# eightbyeight-testcard.net
KiCad netlist of a schematic drawn in EAGLE
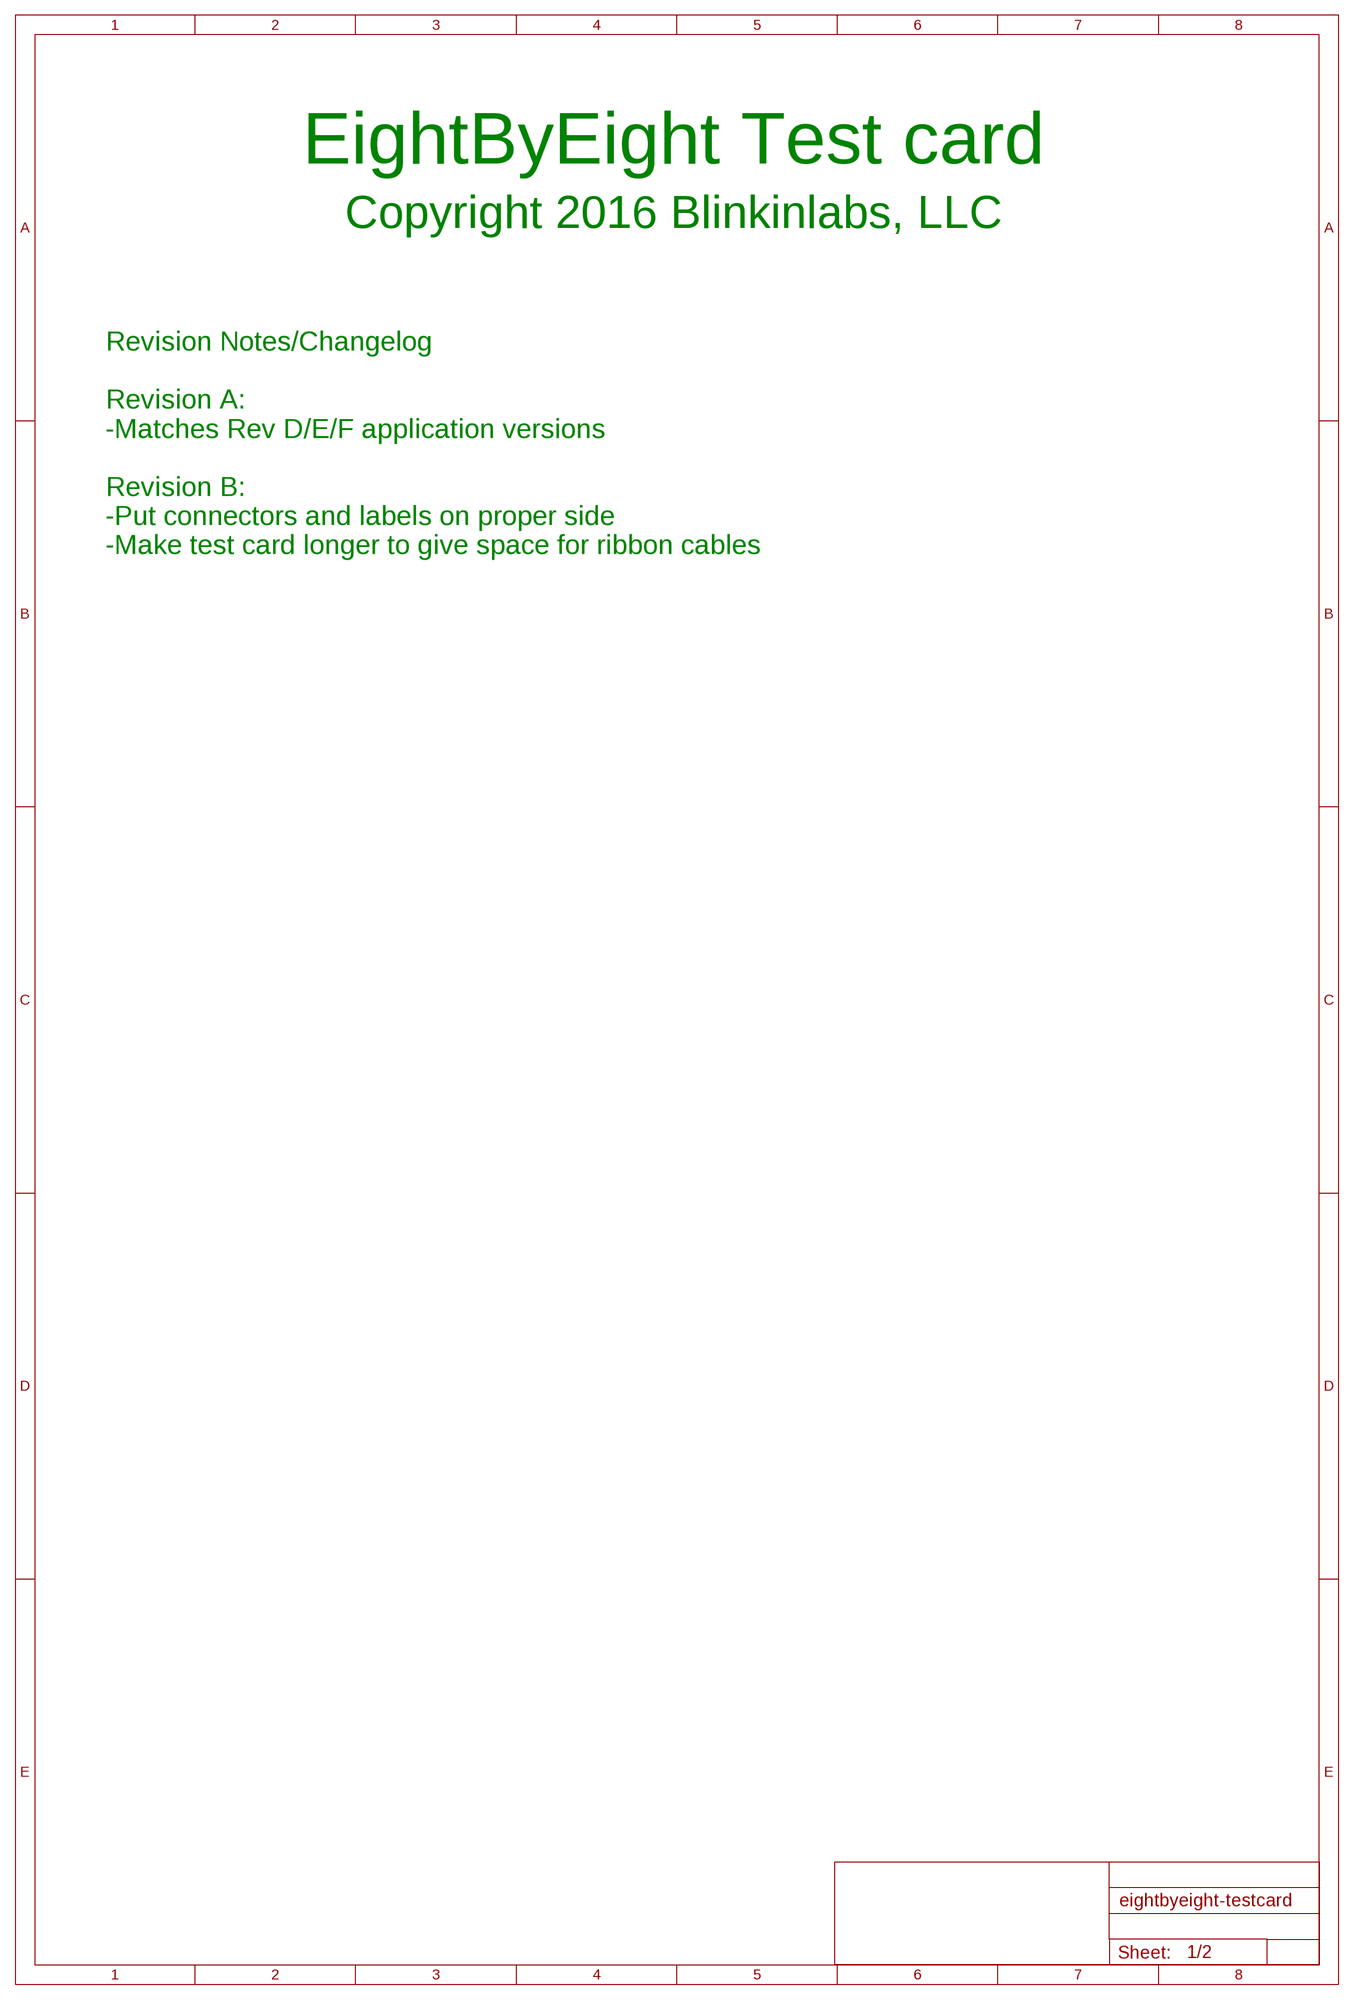
[diagram p0: schematic, sheet 1]
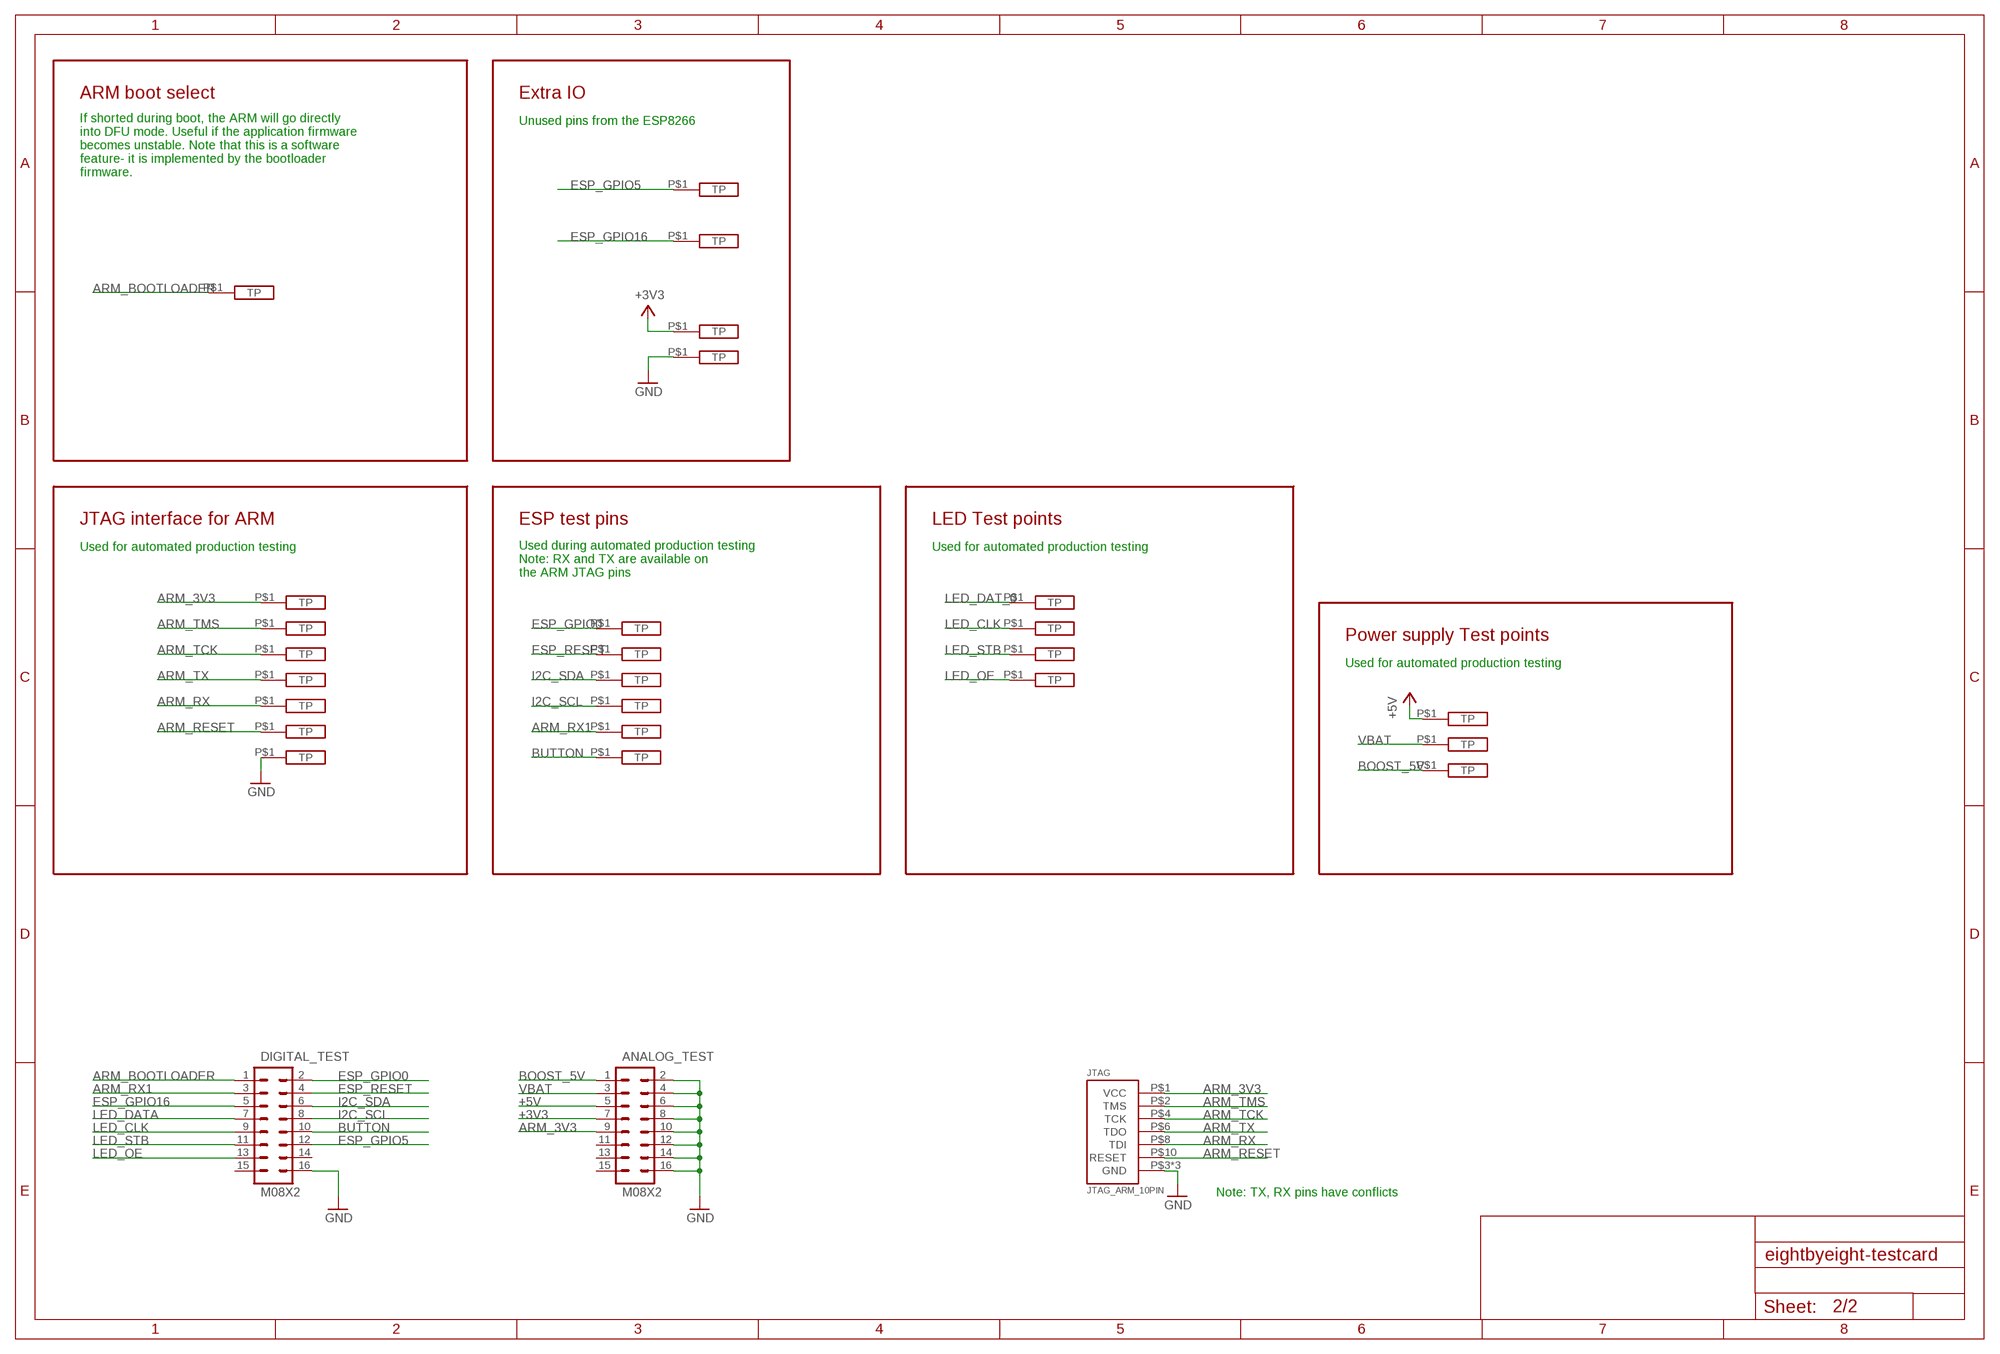
[diagram p1: schematic, sheet 2]

(export (version "E")
  (design (tool "Eeschema 10.0.6"))
  (components
    (comp (ref "+3V3")
      (value "TEST_POINT2.55MM")
      (footprint "eagle-import:IO_HOLE_2.55MM")
      (libsource (lib "eagle-import") (part "TEST_POINT2.55MM"))
    )
    (comp (ref "5V")
      (value "TEST_POINT1.4MM")
      (footprint "eagle-import:IO_HOLE_1.4MM")
      (libsource (lib "eagle-import") (part "TEST_POINT1.4MM"))
    )
    (comp (ref "ANALOG_TEST")
      (value "M08X2")
      (footprint "eagle-import:2X8")
      (libsource (lib "eagle-import") (part "M08X2"))
    )
    (comp (ref "ARM_3V3")
      (value "TEST_POINT1.4MM")
      (footprint "eagle-import:IO_HOLE_1.4MM")
      (libsource (lib "eagle-import") (part "TEST_POINT1.4MM"))
    )
    (comp (ref "ARM_BOOT")
      (value "TEST_POINT1.4MM")
      (footprint "eagle-import:IO_HOLE_1.4MM")
      (libsource (lib "eagle-import") (part "TEST_POINT1.4MM"))
    )
    (comp (ref "ARM_RESET")
      (value "TEST_POINT1.4MM")
      (footprint "eagle-import:IO_HOLE_1.4MM")
      (libsource (lib "eagle-import") (part "TEST_POINT1.4MM"))
    )
    (comp (ref "ARM_RX")
      (value "TEST_POINT1.4MM")
      (footprint "eagle-import:IO_HOLE_1.4MM")
      (libsource (lib "eagle-import") (part "TEST_POINT1.4MM"))
    )
    (comp (ref "ARM_RX1")
      (value "TEST_POINT1.4MM")
      (footprint "eagle-import:IO_HOLE_1.4MM")
      (libsource (lib "eagle-import") (part "TEST_POINT1.4MM"))
    )
    (comp (ref "ARM_TCK")
      (value "TEST_POINT1.4MM")
      (footprint "eagle-import:IO_HOLE_1.4MM")
      (libsource (lib "eagle-import") (part "TEST_POINT1.4MM"))
    )
    (comp (ref "ARM_TMS")
      (value "TEST_POINT1.4MM")
      (footprint "eagle-import:IO_HOLE_1.4MM")
      (libsource (lib "eagle-import") (part "TEST_POINT1.4MM"))
    )
    (comp (ref "ARM_TX")
      (value "TEST_POINT1.4MM")
      (footprint "eagle-import:IO_HOLE_1.4MM")
      (libsource (lib "eagle-import") (part "TEST_POINT1.4MM"))
    )
    (comp (ref "BOOST_5V")
      (value "TEST_POINT1.4MM")
      (footprint "eagle-import:IO_HOLE_1.4MM")
      (libsource (lib "eagle-import") (part "TEST_POINT1.4MM"))
    )
    (comp (ref "BUTTON")
      (value "TEST_POINT1.4MM")
      (footprint "eagle-import:IO_HOLE_1.4MM")
      (libsource (lib "eagle-import") (part "TEST_POINT1.4MM"))
    )
    (comp (ref "DIGITAL_TEST")
      (value "M08X2")
      (footprint "eagle-import:2X8")
      (libsource (lib "eagle-import") (part "M08X2"))
    )
    (comp (ref "ESP_GPIO0")
      (value "TEST_POINT1.4MM")
      (footprint "eagle-import:IO_HOLE_1.4MM")
      (libsource (lib "eagle-import") (part "TEST_POINT1.4MM"))
    )
    (comp (ref "ESP_GPIO5")
      (value "TEST_POINT2.55MM")
      (footprint "eagle-import:IO_HOLE_2.55MM")
      (libsource (lib "eagle-import") (part "TEST_POINT2.55MM"))
    )
    (comp (ref "ESP_GPIO16")
      (value "TEST_POINT2.55MM")
      (footprint "eagle-import:IO_HOLE_2.55MM")
      (libsource (lib "eagle-import") (part "TEST_POINT2.55MM"))
    )
    (comp (ref "ESP_RESET")
      (value "TEST_POINT1.4MM")
      (footprint "eagle-import:IO_HOLE_1.4MM")
      (libsource (lib "eagle-import") (part "TEST_POINT1.4MM"))
    )
    (comp (ref "GND")
      (value "TEST_POINT2.55MM")
      (footprint "eagle-import:IO_HOLE_2.55MM")
      (libsource (lib "eagle-import") (part "TEST_POINT2.55MM"))
    )
    (comp (ref "GND_")
      (value "TEST_POINT1.4MM")
      (footprint "eagle-import:IO_HOLE_1.4MM")
      (libsource (lib "eagle-import") (part "TEST_POINT1.4MM"))
    )
    (comp (ref "I2C_SCL")
      (value "TEST_POINT1.4MM")
      (footprint "eagle-import:IO_HOLE_1.4MM")
      (libsource (lib "eagle-import") (part "TEST_POINT1.4MM"))
    )
    (comp (ref "I2C_SDA")
      (value "TEST_POINT1.4MM")
      (footprint "eagle-import:IO_HOLE_1.4MM")
      (libsource (lib "eagle-import") (part "TEST_POINT1.4MM"))
    )
    (comp (ref "JTAG")
      (value "JTAG_ARM_10PIN")
      (footprint "eagle-import:2X05-1.27MM-SMD")
      (libsource (lib "eagle-import") (part "JTAG_ARM_10PIN"))
    )
    (comp (ref "LED_CLK")
      (value "TEST_POINT1.4MM")
      (footprint "eagle-import:IO_HOLE_1.4MM")
      (libsource (lib "eagle-import") (part "TEST_POINT1.4MM"))
    )
    (comp (ref "LED_DATA")
      (value "TEST_POINT1.4MM")
      (footprint "eagle-import:IO_HOLE_1.4MM")
      (libsource (lib "eagle-import") (part "TEST_POINT1.4MM"))
    )
    (comp (ref "LED_OE")
      (value "TEST_POINT1.4MM")
      (footprint "eagle-import:IO_HOLE_1.4MM")
      (libsource (lib "eagle-import") (part "TEST_POINT1.4MM"))
    )
    (comp (ref "LED_STB")
      (value "TEST_POINT1.4MM")
      (footprint "eagle-import:IO_HOLE_1.4MM")
      (libsource (lib "eagle-import") (part "TEST_POINT1.4MM"))
    )
    (comp (ref "VBAT")
      (value "TEST_POINT1.4MM")
      (footprint "eagle-import:IO_HOLE_1.4MM")
      (libsource (lib "eagle-import") (part "TEST_POINT1.4MM"))
    )
  )
  (nets
    (net (code "1") (name "+3V3") (class "Default")
      (node (ref "+3V3") (pin "P$1") (pinfunction "TP_P$1") (pintype "bidirectional"))
      (node (ref "ANALOG_TEST") (pin "7") (pinfunction "7_7") (pintype "passive"))
    )
    (net (code "2") (name "+5V") (class "Default")
      (node (ref "5V") (pin "P$1") (pinfunction "TP_P$1") (pintype "bidirectional"))
      (node (ref "ANALOG_TEST") (pin "5") (pinfunction "5_5") (pintype "passive"))
    )
    (net (code "3") (name "ARM_3V3") (class "Default")
      (node (ref "ANALOG_TEST") (pin "9") (pinfunction "9_9") (pintype "passive"))
      (node (ref "ARM_3V3") (pin "P$1") (pinfunction "TP_P$1") (pintype "bidirectional"))
      (node (ref "JTAG") (pin "P$1") (pinfunction "VCC_P$1") (pintype "power_in"))
    )
    (net (code "4") (name "ARM_BOOTLOADER") (class "Default")
      (node (ref "ARM_BOOT") (pin "P$1") (pinfunction "TP_P$1") (pintype "bidirectional"))
      (node (ref "DIGITAL_TEST") (pin "1") (pinfunction "1_1") (pintype "passive"))
    )
    (net (code "5") (name "ARM_RESET") (class "Default")
      (node (ref "ARM_RESET") (pin "P$1") (pinfunction "TP_P$1") (pintype "bidirectional"))
      (node (ref "JTAG") (pin "P$10") (pinfunction "RESET_P$10") (pintype "bidirectional"))
    )
    (net (code "6") (name "ARM_RX") (class "Default")
      (node (ref "ARM_RX") (pin "P$1") (pinfunction "TP_P$1") (pintype "bidirectional"))
      (node (ref "JTAG") (pin "P$8") (pinfunction "TDI_P$8") (pintype "bidirectional"))
    )
    (net (code "7") (name "ARM_RX1") (class "Default")
      (node (ref "ARM_RX1") (pin "P$1") (pinfunction "TP_P$1") (pintype "bidirectional"))
      (node (ref "DIGITAL_TEST") (pin "3") (pinfunction "3_3") (pintype "passive"))
    )
    (net (code "8") (name "ARM_TCK") (class "Default")
      (node (ref "ARM_TCK") (pin "P$1") (pinfunction "TP_P$1") (pintype "bidirectional"))
      (node (ref "JTAG") (pin "P$4") (pinfunction "TCK_P$4") (pintype "bidirectional"))
    )
    (net (code "9") (name "ARM_TMS") (class "Default")
      (node (ref "ARM_TMS") (pin "P$1") (pinfunction "TP_P$1") (pintype "bidirectional"))
      (node (ref "JTAG") (pin "P$2") (pinfunction "TMS_P$2") (pintype "bidirectional"))
    )
    (net (code "10") (name "ARM_TX") (class "Default")
      (node (ref "ARM_TX") (pin "P$1") (pinfunction "TP_P$1") (pintype "bidirectional"))
      (node (ref "JTAG") (pin "P$6") (pinfunction "TDO_P$6") (pintype "bidirectional"))
    )
    (net (code "11") (name "BOOST_5V") (class "Default")
      (node (ref "ANALOG_TEST") (pin "1") (pinfunction "1_1") (pintype "passive"))
      (node (ref "BOOST_5V") (pin "P$1") (pinfunction "TP_P$1") (pintype "bidirectional"))
    )
    (net (code "12") (name "BUTTON") (class "Default")
      (node (ref "BUTTON") (pin "P$1") (pinfunction "TP_P$1") (pintype "bidirectional"))
      (node (ref "DIGITAL_TEST") (pin "10") (pinfunction "10_10") (pintype "passive"))
    )
    (net (code "13") (name "ESP_GPIO0") (class "Default")
      (node (ref "DIGITAL_TEST") (pin "2") (pinfunction "2_2") (pintype "passive"))
      (node (ref "ESP_GPIO0") (pin "P$1") (pinfunction "TP_P$1") (pintype "bidirectional"))
    )
    (net (code "14") (name "ESP_GPIO5") (class "Default")
      (node (ref "DIGITAL_TEST") (pin "12") (pinfunction "12_12") (pintype "passive"))
      (node (ref "ESP_GPIO5") (pin "P$1") (pinfunction "TP_P$1") (pintype "bidirectional"))
    )
    (net (code "15") (name "ESP_GPIO16") (class "Default")
      (node (ref "DIGITAL_TEST") (pin "5") (pinfunction "5_5") (pintype "passive"))
      (node (ref "ESP_GPIO16") (pin "P$1") (pinfunction "TP_P$1") (pintype "bidirectional"))
    )
    (net (code "16") (name "ESP_RESET") (class "Default")
      (node (ref "DIGITAL_TEST") (pin "4") (pinfunction "4_4") (pintype "passive"))
      (node (ref "ESP_RESET") (pin "P$1") (pinfunction "TP_P$1") (pintype "bidirectional"))
    )
    (net (code "17") (name "GND") (class "Default")
      (node (ref "ANALOG_TEST") (pin "10") (pinfunction "10_10") (pintype "passive"))
      (node (ref "ANALOG_TEST") (pin "12") (pinfunction "12_12") (pintype "passive"))
      (node (ref "ANALOG_TEST") (pin "14") (pinfunction "14_14") (pintype "passive"))
      (node (ref "ANALOG_TEST") (pin "16") (pinfunction "16_16") (pintype "passive"))
      (node (ref "ANALOG_TEST") (pin "2") (pinfunction "2_2") (pintype "passive"))
      (node (ref "ANALOG_TEST") (pin "4") (pinfunction "4_4") (pintype "passive"))
      (node (ref "ANALOG_TEST") (pin "6") (pinfunction "6_6") (pintype "passive"))
      (node (ref "ANALOG_TEST") (pin "8") (pinfunction "8_8") (pintype "passive"))
      (node (ref "DIGITAL_TEST") (pin "16") (pinfunction "16_16") (pintype "passive"))
      (node (ref "GND") (pin "P$1") (pinfunction "TP_P$1") (pintype "bidirectional"))
      (node (ref "GND_") (pin "P$1") (pinfunction "TP_P$1") (pintype "bidirectional"))
      (node (ref "JTAG") (pin "P$3") (pinfunction "GND_P$3") (pintype "power_in"))
      (node (ref "JTAG") (pin "P$5") (pinfunction "GND_P$5") (pintype "power_in"))
      (node (ref "JTAG") (pin "P$9") (pinfunction "GND_P$9") (pintype "power_in"))
    )
    (net (code "18") (name "I2C_SCL") (class "Default")
      (node (ref "DIGITAL_TEST") (pin "8") (pinfunction "8_8") (pintype "passive"))
      (node (ref "I2C_SCL") (pin "P$1") (pinfunction "TP_P$1") (pintype "bidirectional"))
    )
    (net (code "19") (name "I2C_SDA") (class "Default")
      (node (ref "DIGITAL_TEST") (pin "6") (pinfunction "6_6") (pintype "passive"))
      (node (ref "I2C_SDA") (pin "P$1") (pinfunction "TP_P$1") (pintype "bidirectional"))
    )
    (net (code "20") (name "LED_CLK") (class "Default")
      (node (ref "DIGITAL_TEST") (pin "9") (pinfunction "9_9") (pintype "passive"))
      (node (ref "LED_CLK") (pin "P$1") (pinfunction "TP_P$1") (pintype "bidirectional"))
    )
    (net (code "21") (name "LED_DATA") (class "Default")
      (node (ref "DIGITAL_TEST") (pin "7") (pinfunction "7_7") (pintype "passive"))
    )
    (net (code "22") (name "LED_DAT_0") (class "Default")
      (node (ref "LED_DATA") (pin "P$1") (pinfunction "TP_P$1") (pintype "bidirectional"))
    )
    (net (code "23") (name "LED_OE") (class "Default")
      (node (ref "DIGITAL_TEST") (pin "13") (pinfunction "13_13") (pintype "passive"))
      (node (ref "LED_OE") (pin "P$1") (pinfunction "TP_P$1") (pintype "bidirectional"))
    )
    (net (code "24") (name "LED_STB") (class "Default")
      (node (ref "DIGITAL_TEST") (pin "11") (pinfunction "11_11") (pintype "passive"))
      (node (ref "LED_STB") (pin "P$1") (pinfunction "TP_P$1") (pintype "bidirectional"))
    )
    (net (code "25") (name "VBAT") (class "Default")
      (node (ref "ANALOG_TEST") (pin "3") (pinfunction "3_3") (pintype "passive"))
      (node (ref "VBAT") (pin "P$1") (pinfunction "TP_P$1") (pintype "bidirectional"))
    )
    (net (code "26") (name "unconnected-(ANALOG_TEST-Pad11)") (class "Default")
      (node (ref "ANALOG_TEST") (pin "11") (pinfunction "11_11") (pintype "passive"))
    )
    (net (code "27") (name "unconnected-(ANALOG_TEST-Pad13)") (class "Default")
      (node (ref "ANALOG_TEST") (pin "13") (pinfunction "13_13") (pintype "passive"))
    )
    (net (code "28") (name "unconnected-(ANALOG_TEST-Pad15)") (class "Default")
      (node (ref "ANALOG_TEST") (pin "15") (pinfunction "15_15") (pintype "passive"))
    )
    (net (code "29") (name "unconnected-(DIGITAL_TEST-Pad14)") (class "Default")
      (node (ref "DIGITAL_TEST") (pin "14") (pinfunction "14_14") (pintype "passive"))
    )
    (net (code "30") (name "unconnected-(DIGITAL_TEST-Pad15)") (class "Default")
      (node (ref "DIGITAL_TEST") (pin "15") (pinfunction "15_15") (pintype "passive"))
    )
  )
)
